# 04-BLE.net
KiCad netlist of a schematic drawn in Altium Designer
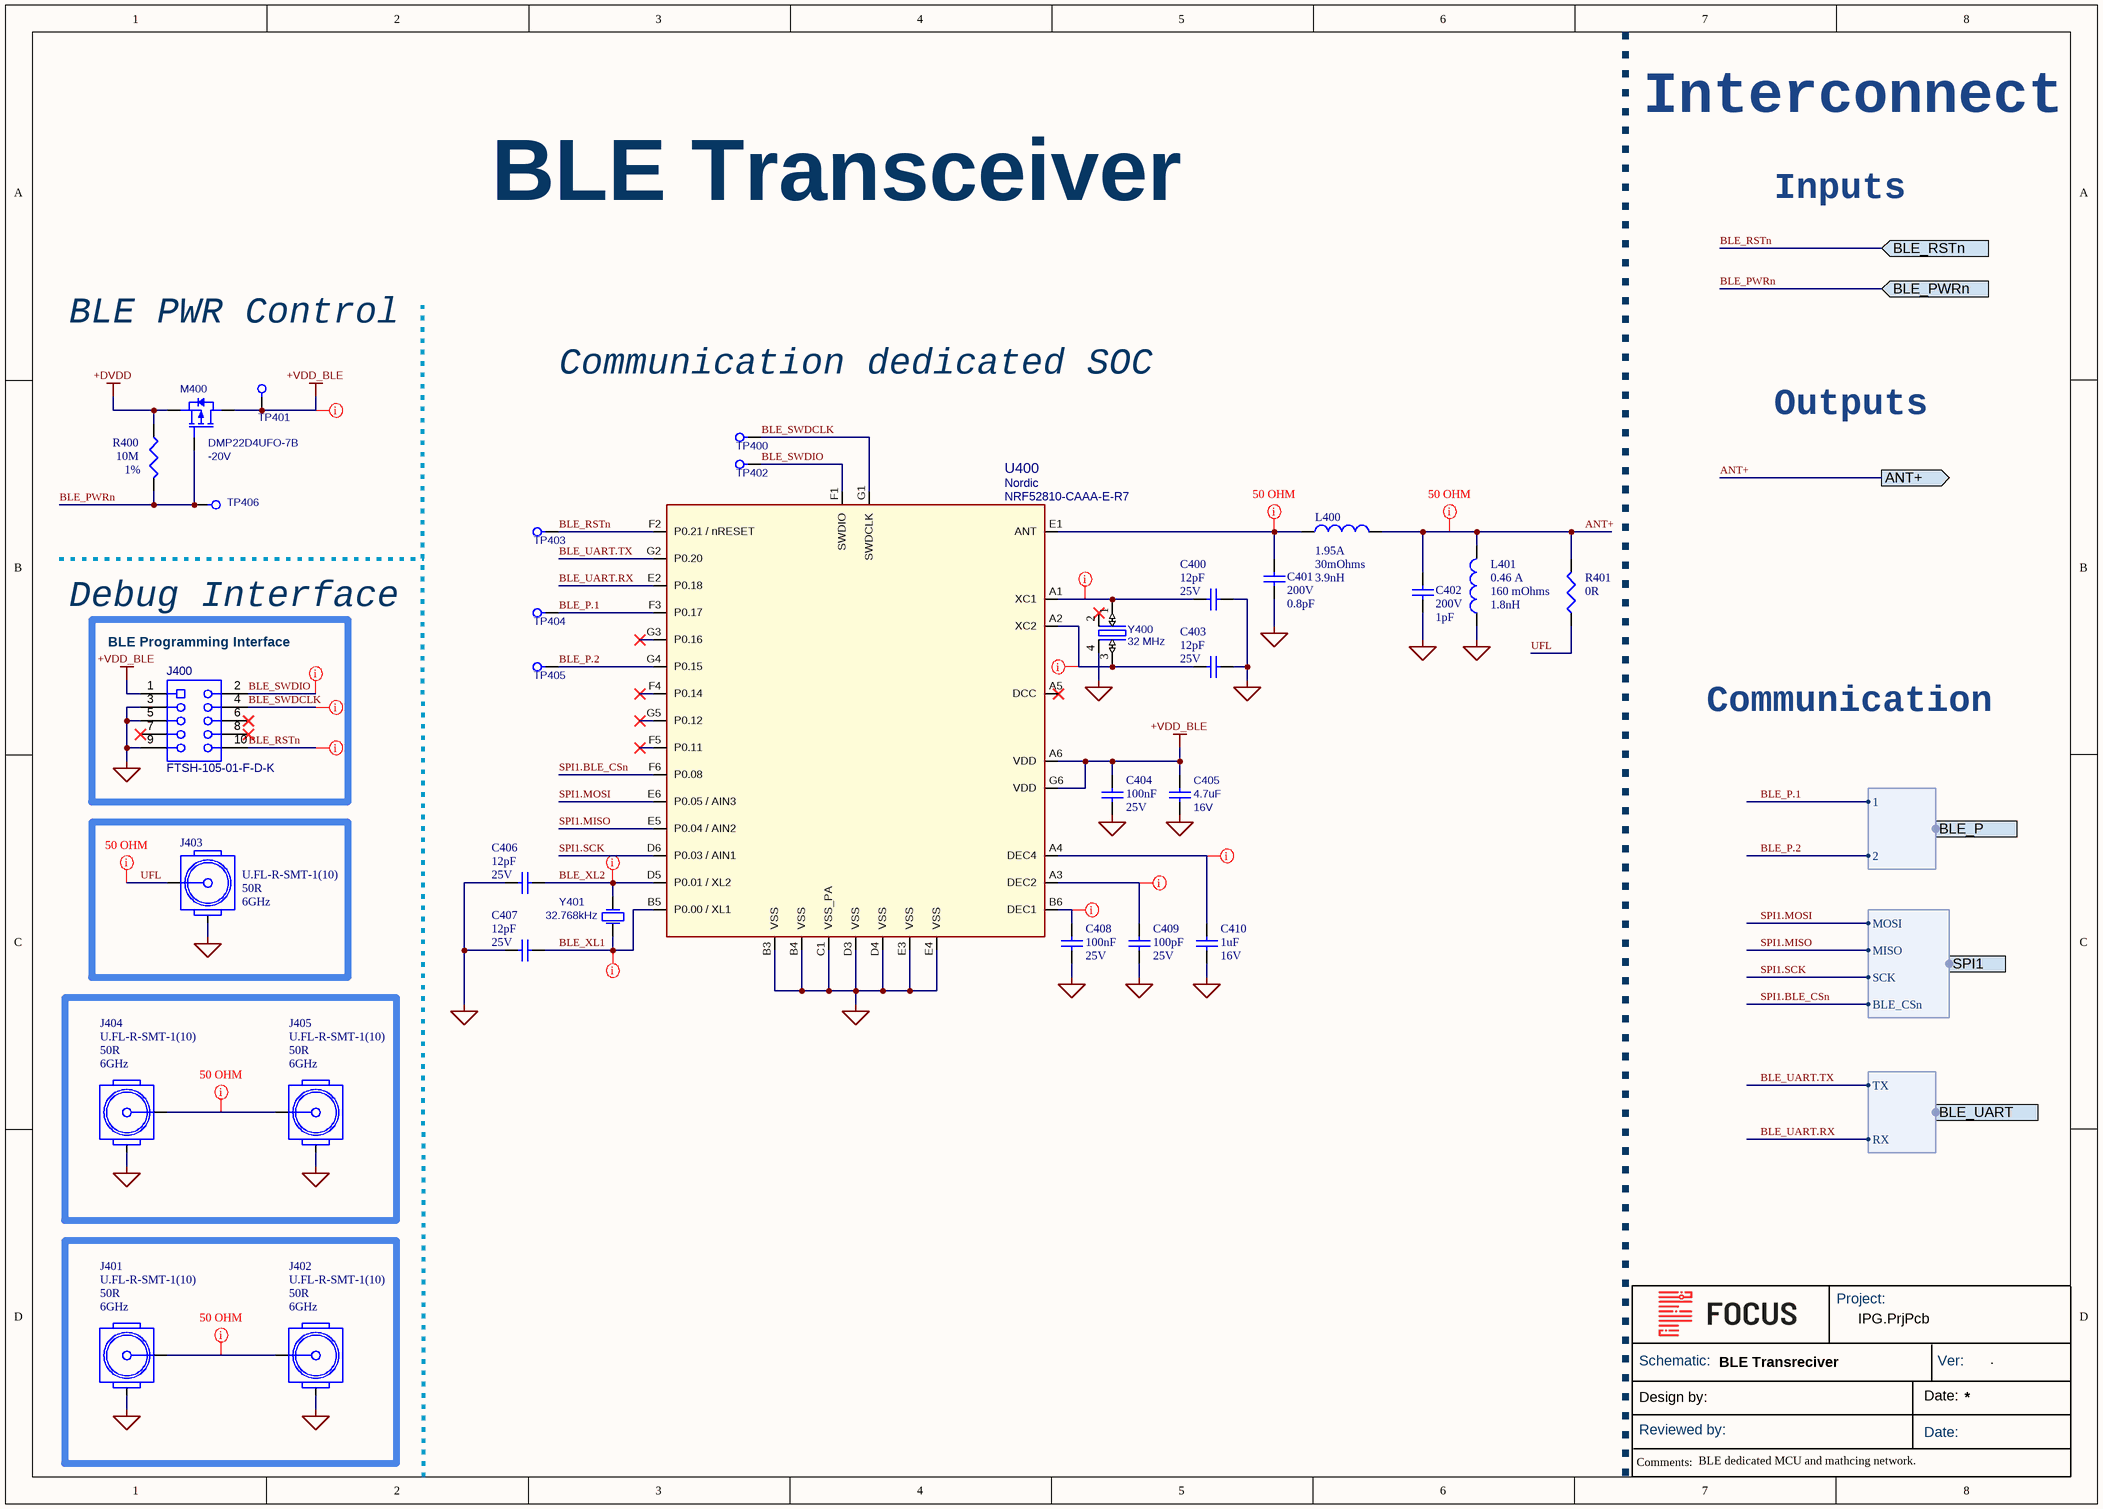
[diagram p0: 04-BLE.SchDoc]

(export (version "E")
  (design (tool "Eeschema 10.0.6"))
  (components
    (comp (ref "C400")
      (value "12pF")
      (footprint "C0201_C")
      (fields
        (field (name "MANUFACTURER") "Murata")
        (field (name "MANUFACTURER PART NUMBER") "GRM0335C1E120JA01D")
        (field (name "RATED DC VOLTAGE (URDC)") "25V")
      )
      (libsource (lib "MP-LIBRARY") (part "GRM0335C1E120JA01D"))
    )
    (comp (ref "C401")
      (value "0.8pF")
      (footprint "CAP0402_REDUCED")
      (description "Capacitor, 0.8pF, Silicon RF, 200V, Tolerance 0.05pF, 0402, Implant-grade")
      (fields
        (field (name "MANUFACTURER") "Kyocera AVX")
        (field (name "MANUFACTURER PART NUMBER") "600L0R8AT200T")
        (field (name "VOLTAGE RATING") "200V")
      )
      (libsource (lib "MP-LIBRARY") (part "600L0R8AT200T"))
    )
    (comp (ref "C402")
      (value "1pF")
      (footprint "CAP0402_REDUCED")
      (description "Capacitor, 1pF, RF Capacitors, 200V, Tolerance 0.01pF, 0402, Implant-grade")
      (fields
        (field (name "MANUFACTURER") "Kyocera AVX")
        (field (name "MANUFACTURER PART NUMBER") "600L1R0AT200T")
        (field (name "VOLTAGE RATING") "200V")
      )
      (libsource (lib "MP-LIBRARY") (part "600L1R0AT200T"))
    )
    (comp (ref "C403")
      (value "12pF")
      (footprint "C0201_C")
      (fields
        (field (name "MANUFACTURER") "Murata")
        (field (name "MANUFACTURER PART NUMBER") "GRM0335C1E120JA01D")
        (field (name "RATED DC VOLTAGE (URDC)") "25V")
      )
      (libsource (lib "MP-LIBRARY") (part "GRM0335C1E120JA01D"))
    )
    (comp (ref "C404")
      (value "100nF")
      (footprint "C0201_C")
      (fields
        (field (name "MANUFACTURER") "Murata")
        (field (name "MANUFACTURER PART NUMBER") "GRM033R61E104KE14J")
        (field (name "RATED DC VOLTAGE (URDC)") "25V")
      )
      (libsource (lib "MP-LIBRARY") (part "GRM033R61E104KE14J"))
    )
    (comp (ref "C405")
      (value "4.7uF")
      (footprint "CAP0603_REDUCED")
      (description "Capacitor, 4.7uF, X5R, 16V, 10%, 0603, Implant-grade")
      (fields
        (field (name "MANUFACTURER") "Murata")
        (field (name "RATING") "16V")
        (field (name "MANUFACTURER PART NUMBER") "GRM188R61C475KE11")
      )
      (libsource (lib "MP-LIBRARY") (part "GRM188R61C475KE11"))
    )
    (comp (ref "C406")
      (value "12pF")
      (footprint "C0201_C")
      (fields
        (field (name "MANUFACTURER") "Murata")
        (field (name "MANUFACTURER PART NUMBER") "GRM0335C1E120JA01D")
        (field (name "RATED DC VOLTAGE (URDC)") "25V")
      )
      (libsource (lib "MP-LIBRARY") (part "GRM0335C1E120JA01D"))
    )
    (comp (ref "C407")
      (value "12pF")
      (footprint "C0201_C")
      (fields
        (field (name "MANUFACTURER") "Murata")
        (field (name "MANUFACTURER PART NUMBER") "GRM0335C1E120JA01D")
        (field (name "RATED DC VOLTAGE (URDC)") "25V")
      )
      (libsource (lib "MP-LIBRARY") (part "GRM0335C1E120JA01D"))
    )
    (comp (ref "C408")
      (value "100nF")
      (footprint "C0201_C")
      (fields
        (field (name "MANUFACTURER") "Murata")
        (field (name "MANUFACTURER PART NUMBER") "GRM033R61E104KE14J")
        (field (name "RATED DC VOLTAGE (URDC)") "25V")
      )
      (libsource (lib "MP-LIBRARY") (part "GRM033R61E104KE14J"))
    )
    (comp (ref "C409")
      (value "100pF")
      (footprint "C0201_C")
      (fields
        (field (name "MANUFACTURER") "Murata")
        (field (name "MANUFACTURER PART NUMBER") "GRM033R71E101KA01D")
        (field (name "RATED DC VOLTAGE (URDC)") "25V")
      )
      (libsource (lib "MP-LIBRARY") (part "GRM033R71E101KA01D"))
    )
    (comp (ref "C410")
      (value "1uF")
      (footprint "C0201_C")
      (fields
        (field (name "MANUFACTURER") "Murata")
        (field (name "MANUFACTURER PART NUMBER") "GRM033R61C105ME15D")
        (field (name "RATED DC VOLTAGE (URDC)") "16V")
      )
      (libsource (lib "MP-LIBRARY") (part "GRM033R61C105ME15D"))
    )
    (comp (ref "J400")
      (value "FTSH-105-01-F-D-K")
      (footprint "SAMTEC_FTSH-105-01-XXX-D-K")
      (description "Connector, 1.27 mm, 2x5, Male, TH")
      (fields (field (name "MANUFACTURER") "Samtec"))
      (libsource (lib "MP-LIBRARY") (part "FTSH-105-01-F-D-K"))
    )
    (comp (ref "J401")
      (value "U.FL-R-SMT-1(10)")
      (footprint "FP-U_FL-R-SMT-1_10-MFG")
      (description "RF Connector, 1 Contact(s), Male, Board Mount, Surface Mount Terminal, Receptacle")
      (fields
        (field (name "MANUFACTURER") "Hirose")
        (field (name "CHARACTERISTIC IMPEDANCE") "50R")
        (field (name "OPERATING FREQUENCY-MAX") "6GHz")
      )
      (libsource (lib "") (part "U.FL-R-SMT-1(10)_1"))
    )
    (comp (ref "J402")
      (value "U.FL-R-SMT-1(10)")
      (footprint "FP-U_FL-R-SMT-1_10-MFG")
      (description "RF Connector, 1 Contact(s), Male, Board Mount, Surface Mount Terminal, Receptacle")
      (fields
        (field (name "MANUFACTURER") "Hirose")
        (field (name "CHARACTERISTIC IMPEDANCE") "50R")
        (field (name "OPERATING FREQUENCY-MAX") "6GHz")
      )
      (libsource (lib "MP-LIBRARY") (part "U.FL-R-SMT-1(10)"))
    )
    (comp (ref "J403")
      (value "U.FL-R-SMT-1(10)")
      (footprint "FP-U_FL-R-SMT-1_10-MFG")
      (description "RF Connector, 1 Contact(s), Male, Board Mount, Surface Mount Terminal, Receptacle")
      (fields
        (field (name "MANUFACTURER") "Hirose")
        (field (name "CHARACTERISTIC IMPEDANCE") "50R")
        (field (name "OPERATING FREQUENCY-MAX") "6GHz")
      )
      (libsource (lib "MP-LIBRARY") (part "U.FL-R-SMT-1(10)"))
    )
    (comp (ref "J404")
      (value "U.FL-R-SMT-1(10)")
      (footprint "FP-U_FL-R-SMT-1_10-MFG")
      (description "RF Connector, 1 Contact(s), Male, Board Mount, Surface Mount Terminal, Receptacle")
      (fields
        (field (name "MANUFACTURER") "Hirose")
        (field (name "CHARACTERISTIC IMPEDANCE") "50R")
        (field (name "OPERATING FREQUENCY-MAX") "6GHz")
      )
      (libsource (lib "") (part "U.FL-R-SMT-1(10)_1"))
    )
    (comp (ref "J405")
      (value "U.FL-R-SMT-1(10)")
      (footprint "FP-U_FL-R-SMT-1_10-MFG")
      (description "RF Connector, 1 Contact(s), Male, Board Mount, Surface Mount Terminal, Receptacle")
      (fields
        (field (name "MANUFACTURER") "Hirose")
        (field (name "CHARACTERISTIC IMPEDANCE") "50R")
        (field (name "OPERATING FREQUENCY-MAX") "6GHz")
      )
      (libsource (lib "MP-LIBRARY") (part "U.FL-R-SMT-1(10)"))
    )
    (comp (ref "L400")
      (value "3.9nH")
      (footprint "L0402_C")
      (description "Inductor, 3.9nH, 1.95A, 2%, 0402")
      (fields
        (field (name "MANUFACTURER") "Murata")
        (field (name "MANUFACTURER PART NUMBER") "LQW15AN3N9G80D")
        (field (name "CURRENT RATING") "1.95A")
        (field (name "DC RESISTANCE") "30mOhms")
      )
      (libsource (lib "MP-LIBRARY") (part "LQW15AN3N9G80D"))
    )
    (comp (ref "L401")
      (value "1.8nH")
      (footprint "L0402_C")
      (description "Inductor, 1.8nH, 0.46A, Tolerance 0.2 nH, 0402")
      (fields
        (field (name "MANUFACTURER") "Murata")
        (field (name "MANUFACTURER PART NUMBER") "LQW15AN1N8C00D")
        (field (name "CURRENT RATING") "0.46 A")
        (field (name "DC RESISTANCE") "160 mOhms")
      )
      (libsource (lib "MP-LIBRARY") (part "LQW15AN1N8C00D"))
    )
    (comp (ref "M400")
      (value "DMP22D4UFO-7B")
      (footprint "DIODESINC_X2-DFN0604-3")
      (description "MOSFET, P-chan, -20V, -383mA, DFN0604")
      (fields (field (name "MANUFACTURER") "Diodes Inc") (field (name "RATING") "-20V"))
      (libsource (lib "MP-LIBRARY") (part "DMP22D4UFO-7B"))
    )
    (comp (ref "R400")
      (value "10M")
      (footprint "R0201_C")
      (fields
        (field (name "MANUFACTURER") "Vishay Draloric")
        (field (name "MANUFACTURER PART NUMBER") "CRCW020110M0FNED")
        (field (name "TOLERANCE") "1%")
        (field (name "POWER") "50mW")
      )
      (libsource (lib "MP-LIBRARY") (part "CRCW020110M0FNED"))
    )
    (comp (ref "R401")
      (value "0R")
      (footprint "R0201_C")
      (description "Resistor, 0 Ohm, 0201, Metal element, Non-Implant grade,")
      (fields
        (field (name "MANUFACTURER") "YAGEO")
        (field (name "MANUFACTURER PART NUMBER") "PA0201-R-070RL")
      )
      (libsource (lib "MP-LIBRARY") (part "PA0201-R-070RL"))
    )
    (comp (ref "TP400")
      (value "Test Point")
      (footprint "testpad_0.9mm")
      (description "Test pad, 0.90mm circular pad")
      (libsource (lib "MP-LIBRARY") (part "Test Point"))
    )
    (comp (ref "TP401")
      (value "Test Point")
      (footprint "testpad_0.9mm")
      (description "Test pad, 0.90mm circular pad")
      (libsource (lib "MP-LIBRARY") (part "Test Point"))
    )
    (comp (ref "TP402")
      (value "Test Point")
      (footprint "testpad_0.9mm")
      (description "Test pad, 0.90mm circular pad")
      (libsource (lib "MP-LIBRARY") (part "Test Point"))
    )
    (comp (ref "TP403")
      (value "Test Point")
      (footprint "testpad_0.9mm")
      (description "Test pad, 0.90mm circular pad")
      (libsource (lib "MP-LIBRARY") (part "Test Point"))
    )
    (comp (ref "TP404")
      (value "Test Point")
      (footprint "testpad_0.9mm")
      (description "Test pad, 0.90mm circular pad")
      (libsource (lib "MP-LIBRARY") (part "Test Point"))
    )
    (comp (ref "TP405")
      (value "Test Point")
      (footprint "testpad_0.9mm")
      (description "Test pad, 0.90mm circular pad")
      (libsource (lib "MP-LIBRARY") (part "Test Point"))
    )
    (comp (ref "TP406")
      (value "Test Point")
      (footprint "testpad_0.9mm")
      (description "Test pad, 0.90mm circular pad")
      (libsource (lib "MP-LIBRARY") (part "Test Point"))
    )
    (comp (ref "U400")
      (value "NRF52810-CAAA-E-R7")
      (footprint "NORDIC_WLCSP_2.482x2.464")
      (description "Bluetooth radio, v5.0, 192 kB Flash, 24 kB RAM, BGA-33")
      (fields (field (name "MANUFACTURER") "Nordic"))
      (libsource (lib "MP-LIBRARY") (part "NRF52810-CAAA-E-R7"))
    )
    (comp (ref "Y400")
      (value "32 MHz")
      (footprint "XTAL_ECS-SMD-CRYSTAL-10-48-CKY-TR")
      (description "32 MHz Â±10ppm Crystal 10pF 100 Ohms 4-SMD, No Lead")
      (fields
        (field (name "MANUFACTURER") "ECS Inc.")
        (field (name "MANUFACTURER PART NUMBER") "ECS-320-10-48-CKY-TR")
      )
      (libsource (lib "MP-LIBRARY") (part "ECS-320-10-48-CKY-TR"))
    )
    (comp (ref "Y401")
      (value "32.768kHz")
      (footprint "MICROCRYSTAL_CC8V-T1A")
      (description "CRYSTAL 32.7680KHZ 6PF SMD")
      (fields
        (field (name "MANUFACTURER") "Micro Crystal")
        (field (name "MANUFACTURER PART NUMBER") "CM8V-T1A-32.768KHZ-6PF-20PPM-TA-QC")
      )
      (libsource (lib "MP-LIBRARY") (part "CM8V-T1A-32.768KHZ-6PF-20PPM-TA-QC"))
    )
  )
  (nets
    (net (code "5") (name "+DVDD") (class "Default")
      (node (ref "M400") (pin "2") (pinfunction "S_2") (pintype "passive"))
      (node (ref "R400") (pin "1") (pinfunction "1_1") (pintype "passive"))
    )
    (net (code "6") (name "+VDD_BLE") (class "Default")
      (node (ref "C404") (pin "2") (pinfunction "2_2") (pintype "passive"))
      (node (ref "C405") (pin "1") (pinfunction "1_1") (pintype "passive"))
      (node (ref "J400") (pin "1") (pinfunction "1_1") (pintype "passive"))
      (node (ref "M400") (pin "3") (pinfunction "D_3") (pintype "passive"))
      (node (ref "TP401") (pin "1") (pinfunction "1_1") (pintype "passive"))
      (node (ref "U400") (pin "A6") (pinfunction "VDD_A6") (pintype "passive"))
      (node (ref "U400") (pin "G6") (pinfunction "VDD_G6") (pintype "passive"))
    )
    (net (code "7") (name "/ANT+") (class "Default")
      (node (ref "C402") (pin "2") (pinfunction "2_2") (pintype "passive"))
      (node (ref "L400") (pin "2") (pinfunction "2_2") (pintype "passive"))
      (node (ref "L401") (pin "2") (pinfunction "2_2") (pintype "passive"))
      (node (ref "R401") (pin "2") (pinfunction "2_2") (pintype "passive"))
    )
    (net (code "8") (name "/BLE_P.1") (class "Default")
      (node (ref "TP404") (pin "1") (pinfunction "1_1") (pintype "passive"))
      (node (ref "U400") (pin "F3") (pinfunction "P0.17_F3") (pintype "passive"))
    )
    (net (code "9") (name "/BLE_P.2") (class "Default")
      (node (ref "TP405") (pin "1") (pinfunction "1_1") (pintype "passive"))
      (node (ref "U400") (pin "G4") (pinfunction "P0.15_G4") (pintype "passive"))
    )
    (net (code "10") (name "/BLE_PWRn") (class "Default")
      (node (ref "M400") (pin "1") (pinfunction "G_1") (pintype "passive"))
      (node (ref "R400") (pin "2") (pinfunction "2_2") (pintype "passive"))
      (node (ref "TP406") (pin "1") (pinfunction "1_1") (pintype "passive"))
    )
    (net (code "11") (name "/BLE_RSTn") (class "Default")
      (node (ref "J400") (pin "10") (pinfunction "10_10") (pintype "passive"))
      (node (ref "TP403") (pin "1") (pinfunction "1_1") (pintype "passive"))
      (node (ref "U400") (pin "F2") (pinfunction "P0.21_/_nRESET_F2") (pintype "passive"))
    )
    (net (code "12") (name "/BLE_SWDCLK") (class "Default")
      (node (ref "J400") (pin "4") (pinfunction "4_4") (pintype "passive"))
      (node (ref "TP400") (pin "1") (pinfunction "1_1") (pintype "passive"))
      (node (ref "U400") (pin "G1") (pinfunction "SWDCLK_G1") (pintype "passive"))
    )
    (net (code "13") (name "/BLE_SWDIO") (class "Default")
      (node (ref "J400") (pin "2") (pinfunction "2_2") (pintype "passive"))
      (node (ref "TP402") (pin "1") (pinfunction "1_1") (pintype "passive"))
      (node (ref "U400") (pin "F1") (pinfunction "SWDIO_F1") (pintype "passive"))
    )
    (net (code "14") (name "/BLE_UART.RX") (class "Default")
      (node (ref "U400") (pin "E2") (pinfunction "P0.18_E2") (pintype "passive"))
    )
    (net (code "15") (name "/BLE_UART.TX") (class "Default")
      (node (ref "U400") (pin "G2") (pinfunction "P0.20_G2") (pintype "passive"))
    )
    (net (code "16") (name "/BLE_XL1") (class "Default")
      (node (ref "C407") (pin "2") (pinfunction "2_2") (pintype "passive"))
      (node (ref "U400") (pin "B5") (pinfunction "P0.00_/_XL1_B5") (pintype "passive"))
      (node (ref "Y401") (pin "1") (pinfunction "1_1") (pintype "passive"))
    )
    (net (code "17") (name "/BLE_XL2") (class "Default")
      (node (ref "C406") (pin "2") (pinfunction "2_2") (pintype "passive"))
      (node (ref "U400") (pin "D5") (pinfunction "P0.01_/_XL2_D5") (pintype "passive"))
      (node (ref "Y401") (pin "2") (pinfunction "2_2") (pintype "passive"))
    )
    (net (code "18") (name "/SPI1.BLE_CSn") (class "Default")
      (node (ref "U400") (pin "F6") (pinfunction "P0.08_F6") (pintype "passive"))
    )
    (net (code "19") (name "/SPI1.MISO") (class "Default")
      (node (ref "U400") (pin "E5") (pinfunction "P0.04_/_AIN2_E5") (pintype "passive"))
    )
    (net (code "20") (name "/SPI1.MOSI") (class "Default")
      (node (ref "U400") (pin "E6") (pinfunction "P0.05_/_AIN3_E6") (pintype "passive"))
    )
    (net (code "21") (name "/SPI1.SCK") (class "Default")
      (node (ref "U400") (pin "D6") (pinfunction "P0.03_/_AIN1_D6") (pintype "passive"))
    )
    (net (code "22") (name "/UFL") (class "Default")
      (node (ref "J403") (pin "1") (pinfunction "1_1") (pintype "passive"))
      (node (ref "R401") (pin "1") (pinfunction "1_1") (pintype "passive"))
    )
    (net (code "26") (name "GND") (class "Default")
      (node (ref "C400") (pin "2") (pinfunction "2_2") (pintype "passive"))
      (node (ref "C401") (pin "1") (pinfunction "1_1") (pintype "passive"))
      (node (ref "C402") (pin "1") (pinfunction "1_1") (pintype "passive"))
      (node (ref "C403") (pin "2") (pinfunction "2_2") (pintype "passive"))
      (node (ref "C404") (pin "1") (pinfunction "1_1") (pintype "passive"))
      (node (ref "C405") (pin "2") (pinfunction "2_2") (pintype "passive"))
      (node (ref "C406") (pin "1") (pinfunction "1_1") (pintype "passive"))
      (node (ref "C407") (pin "1") (pinfunction "1_1") (pintype "passive"))
      (node (ref "C408") (pin "1") (pinfunction "1_1") (pintype "passive"))
      (node (ref "C409") (pin "1") (pinfunction "1_1") (pintype "passive"))
      (node (ref "C410") (pin "2") (pinfunction "2_2") (pintype "passive"))
      (node (ref "J400") (pin "3") (pinfunction "3_3") (pintype "passive"))
      (node (ref "J400") (pin "5") (pinfunction "5_5") (pintype "passive"))
      (node (ref "J400") (pin "9") (pinfunction "9_9") (pintype "passive"))
      (node (ref "J401") (pin "2") (pinfunction "2_2") (pintype "passive"))
      (node (ref "J402") (pin "2") (pinfunction "2_2") (pintype "passive"))
      (node (ref "J403") (pin "2") (pinfunction "2_2") (pintype "passive"))
      (node (ref "J404") (pin "2") (pinfunction "2_2") (pintype "passive"))
      (node (ref "J405") (pin "2") (pinfunction "2_2") (pintype "passive"))
      (node (ref "L401") (pin "1") (pinfunction "1_1") (pintype "passive"))
      (node (ref "U400") (pin "B3") (pinfunction "VSS_B3") (pintype "passive"))
      (node (ref "U400") (pin "B4") (pinfunction "VSS_B4") (pintype "passive"))
      (node (ref "U400") (pin "C1") (pinfunction "VSS_PA_C1") (pintype "passive"))
      (node (ref "U400") (pin "D3") (pinfunction "VSS_D3") (pintype "passive"))
      (node (ref "U400") (pin "D4") (pinfunction "VSS_D4") (pintype "passive"))
      (node (ref "U400") (pin "E3") (pinfunction "VSS_E3") (pintype "passive"))
      (node (ref "U400") (pin "E4") (pinfunction "VSS_E4") (pintype "passive"))
      (node (ref "Y400") (pin "4") (pinfunction "GND_4") (pintype "passive"))
    )
    (net (code "27") (name "Net-(J401-Pad1)") (class "Default")
      (node (ref "J401") (pin "1") (pinfunction "1_1") (pintype "passive"))
      (node (ref "J402") (pin "1") (pinfunction "1_1") (pintype "passive"))
    )
    (net (code "28") (name "Net-(J404-Pad1)") (class "Default")
      (node (ref "J404") (pin "1") (pinfunction "1_1") (pintype "passive"))
      (node (ref "J405") (pin "1") (pinfunction "1_1") (pintype "passive"))
    )
    (net (code "29") (name "Net-(U400-ANT)") (class "Default")
      (node (ref "C401") (pin "2") (pinfunction "2_2") (pintype "passive"))
      (node (ref "L400") (pin "1") (pinfunction "1_1") (pintype "passive"))
      (node (ref "U400") (pin "E1") (pinfunction "ANT_E1") (pintype "passive"))
    )
    (net (code "30") (name "Net-(U400-DEC1)") (class "Default")
      (node (ref "C408") (pin "2") (pinfunction "2_2") (pintype "passive"))
      (node (ref "U400") (pin "B6") (pinfunction "DEC1_B6") (pintype "passive"))
    )
    (net (code "31") (name "Net-(U400-DEC2)") (class "Default")
      (node (ref "C409") (pin "2") (pinfunction "2_2") (pintype "passive"))
      (node (ref "U400") (pin "A3") (pinfunction "DEC2_A3") (pintype "passive"))
    )
    (net (code "32") (name "Net-(U400-DEC4)") (class "Default")
      (node (ref "C410") (pin "1") (pinfunction "1_1") (pintype "passive"))
      (node (ref "U400") (pin "A4") (pinfunction "DEC4_A4") (pintype "passive"))
    )
    (net (code "33") (name "Net-(U400-XC1)") (class "Default")
      (node (ref "C400") (pin "1") (pinfunction "1_1") (pintype "passive"))
      (node (ref "U400") (pin "A1") (pinfunction "XC1_A1") (pintype "passive"))
      (node (ref "Y400") (pin "1") (pinfunction "IN/OUT_1") (pintype "bidirectional"))
    )
    (net (code "34") (name "Net-(U400-XC2)") (class "Default")
      (node (ref "C403") (pin "1") (pinfunction "1_1") (pintype "passive"))
      (node (ref "U400") (pin "A2") (pinfunction "XC2_A2") (pintype "passive"))
      (node (ref "Y400") (pin "3") (pinfunction "OUT/IN_3") (pintype "bidirectional"))
    )
    (net (code "35") (name "unconnected-(J400-Pad6)") (class "Default")
      (node (ref "J400") (pin "6") (pinfunction "6_6") (pintype "passive+no_connect"))
    )
    (net (code "36") (name "unconnected-(J400-Pad7)") (class "Default")
      (node (ref "J400") (pin "7") (pinfunction "7_7") (pintype "passive+no_connect"))
    )
    (net (code "37") (name "unconnected-(J400-Pad8)") (class "Default")
      (node (ref "J400") (pin "8") (pinfunction "8_8") (pintype "passive+no_connect"))
    )
    (net (code "38") (name "unconnected-(U400-DCC-PadA5)") (class "Default")
      (node (ref "U400") (pin "A5") (pinfunction "DCC_A5") (pintype "passive+no_connect"))
    )
    (net (code "39") (name "unconnected-(U400-P0.11-PadF5)") (class "Default")
      (node (ref "U400") (pin "F5") (pinfunction "P0.11_F5") (pintype "passive+no_connect"))
    )
    (net (code "40") (name "unconnected-(U400-P0.12-PadG5)") (class "Default")
      (node (ref "U400") (pin "G5") (pinfunction "P0.12_G5") (pintype "passive+no_connect"))
    )
    (net (code "41") (name "unconnected-(U400-P0.14-PadF4)") (class "Default")
      (node (ref "U400") (pin "F4") (pinfunction "P0.14_F4") (pintype "passive+no_connect"))
    )
    (net (code "42") (name "unconnected-(U400-P0.16-PadG3)") (class "Default")
      (node (ref "U400") (pin "G3") (pinfunction "P0.16_G3") (pintype "passive+no_connect"))
    )
    (net (code "43") (name "unconnected-(Y400-NC-Pad2)") (class "Default")
      (node (ref "Y400") (pin "2") (pinfunction "NC_2") (pintype "passive+no_connect"))
    )
  )
)
